# GSE_Analog_Remote_TOP_Schematic_v1_EasyE.net
KiCad netlist of a schematic drawn in EasyEDA
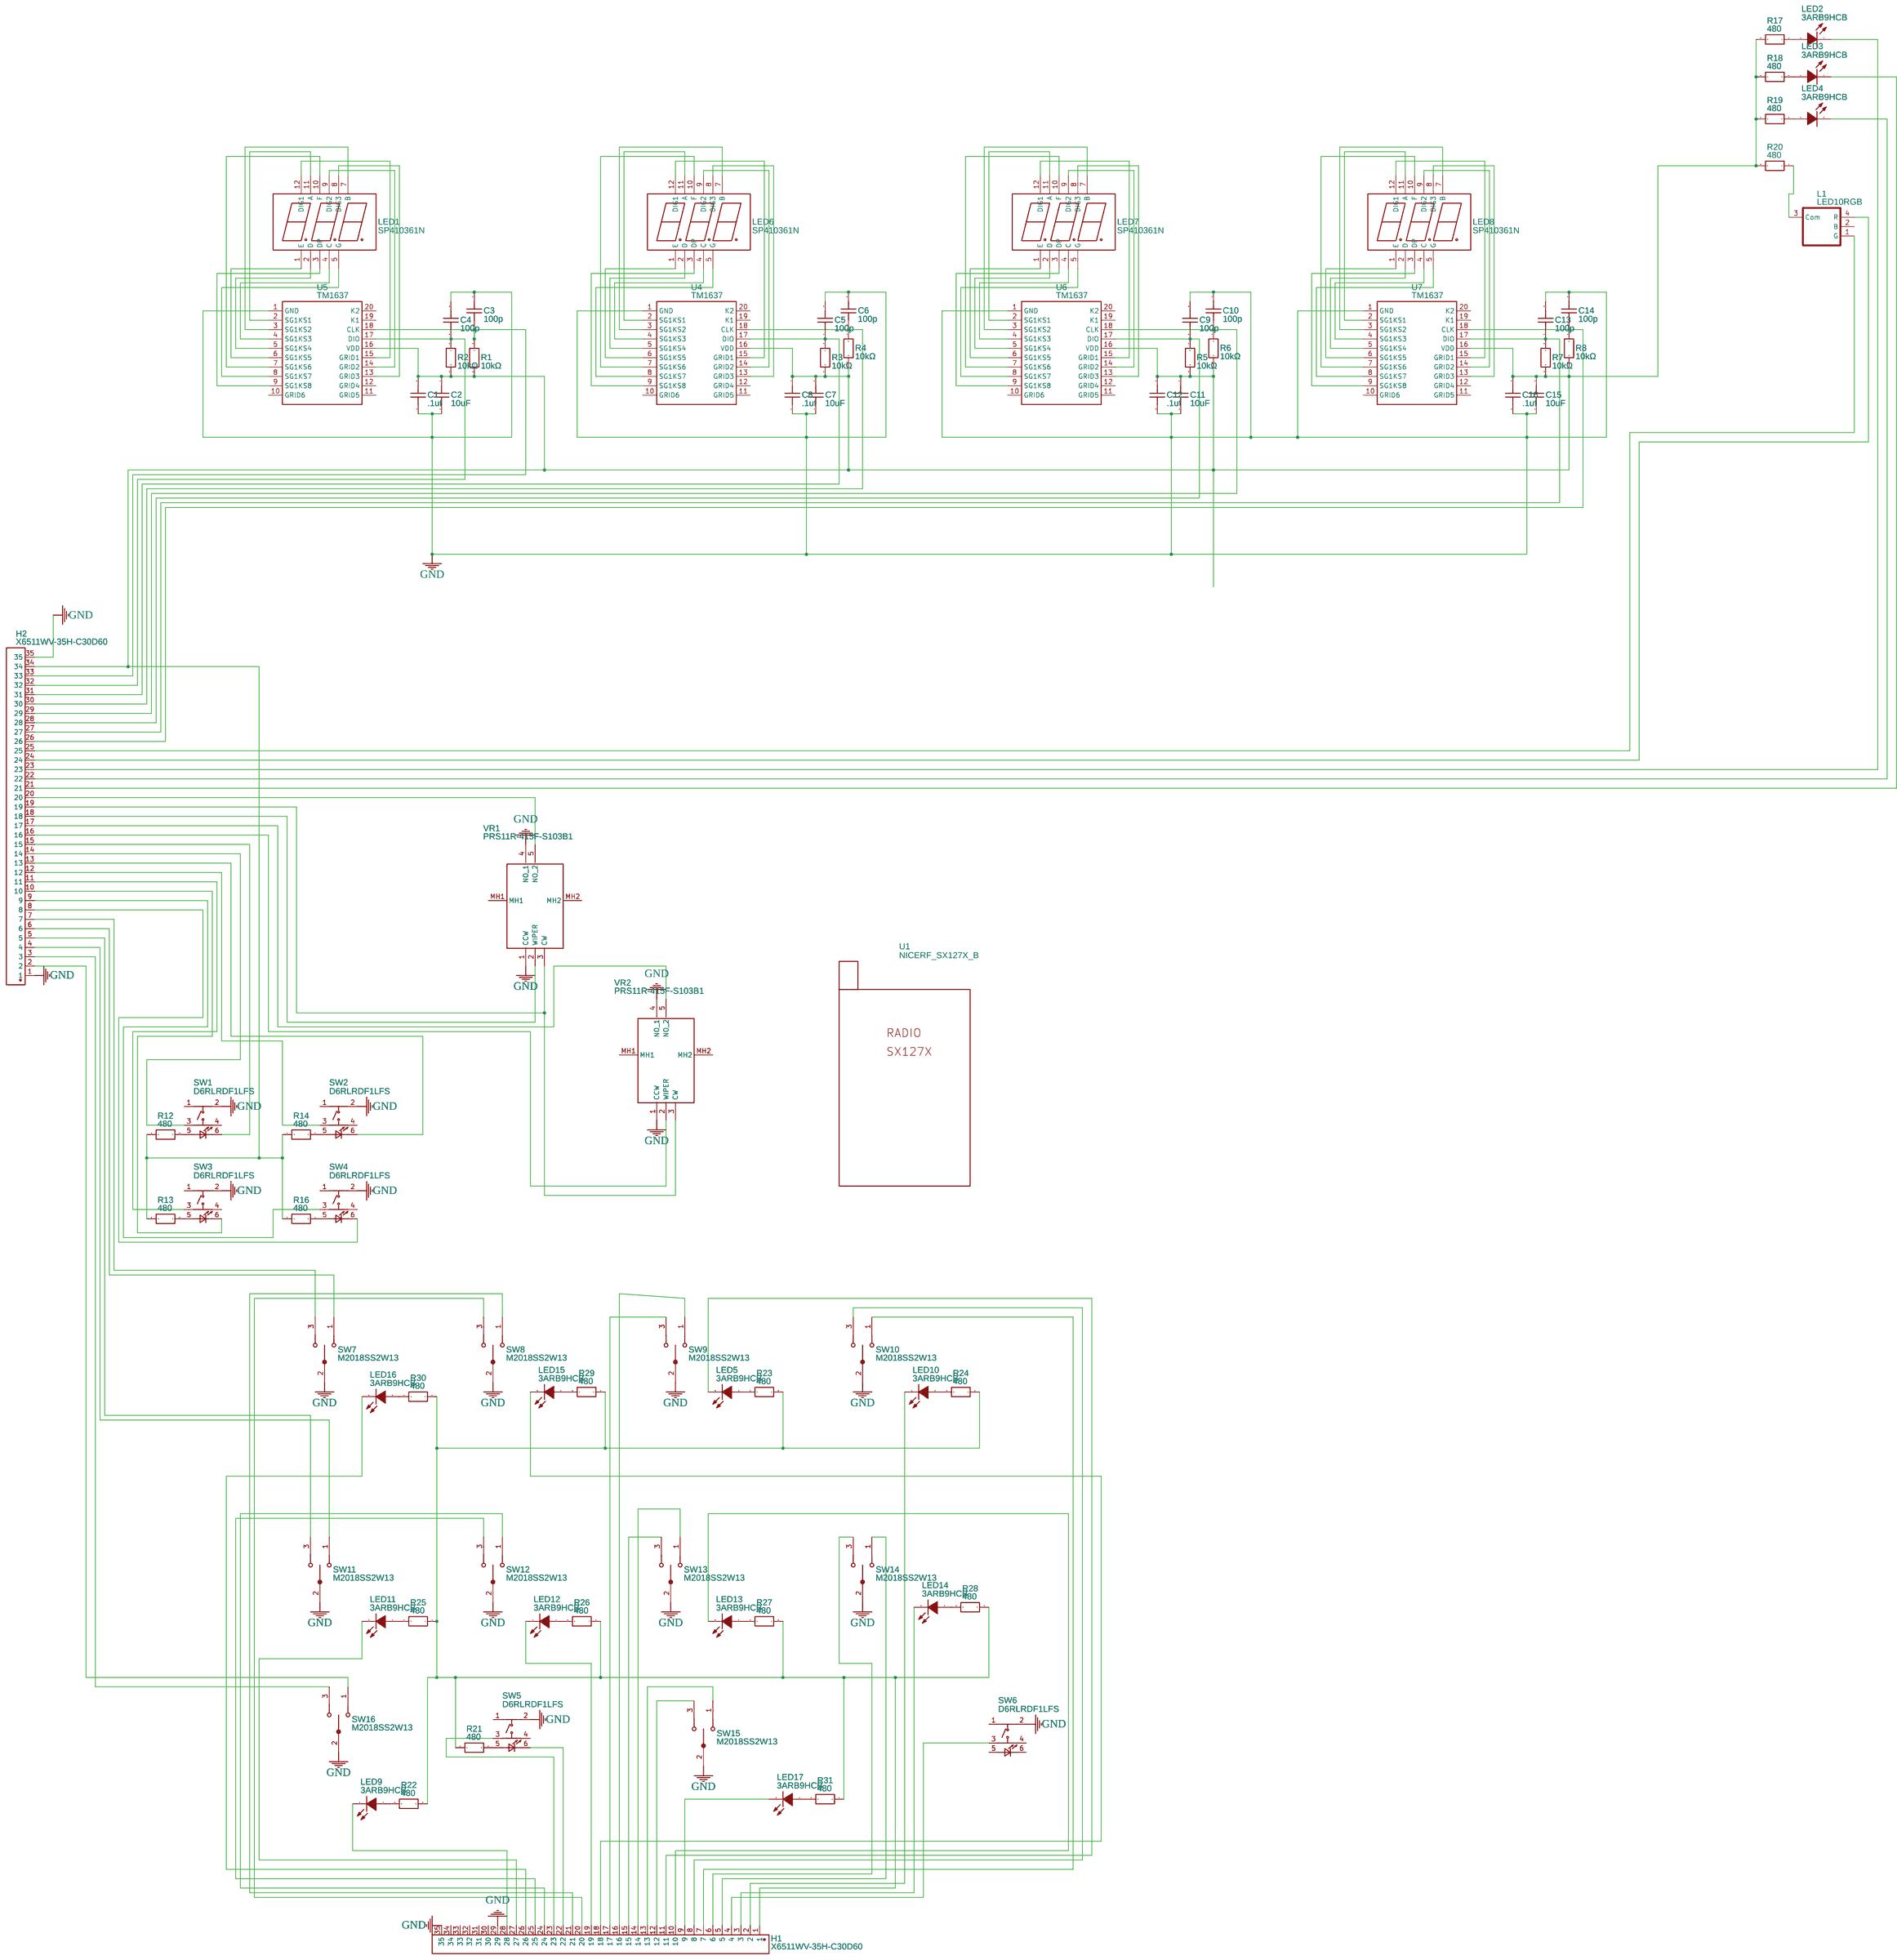
[diagram p0: schematic sheet]

(export (version "E")
  (design (tool "Eeschema 10.0.6"))
  (components
    (comp (ref "C1")
      (value ".1uf")
      (fields (field (name "Manufacturer") "SAMSUNG(三星)"))
      (libsource (lib "") (part "10UF"))
    )
    (comp (ref "C2")
      (value "10uF")
      (fields (field (name "Manufacturer") "SAMSUNG(三星)"))
      (libsource (lib "") (part "10UF"))
    )
    (comp (ref "C3")
      (value "100p")
      (fields (field (name "Manufacturer") "SAMSUNG(三星)"))
      (libsource (lib "") (part "10UF"))
    )
    (comp (ref "C4")
      (value "100p")
      (fields (field (name "Manufacturer") "SAMSUNG(三星)"))
      (libsource (lib "") (part "10UF"))
    )
    (comp (ref "C5")
      (value "100p")
      (fields (field (name "Manufacturer") "SAMSUNG(三星)"))
      (libsource (lib "") (part "10UF"))
    )
    (comp (ref "C6")
      (value "100p")
      (fields (field (name "Manufacturer") "SAMSUNG(三星)"))
      (libsource (lib "") (part "10UF"))
    )
    (comp (ref "C7")
      (value "10uF")
      (fields (field (name "Manufacturer") "SAMSUNG(三星)"))
      (libsource (lib "") (part "10UF"))
    )
    (comp (ref "C8")
      (value ".1uf")
      (fields (field (name "Manufacturer") "SAMSUNG(三星)"))
      (libsource (lib "") (part "10UF"))
    )
    (comp (ref "C9")
      (value "100p")
      (fields (field (name "Manufacturer") "SAMSUNG(三星)"))
      (libsource (lib "") (part "10UF"))
    )
    (comp (ref "C10")
      (value "100p")
      (fields (field (name "Manufacturer") "SAMSUNG(三星)"))
      (libsource (lib "") (part "10UF"))
    )
    (comp (ref "C11")
      (value "10uF")
      (fields (field (name "Manufacturer") "SAMSUNG(三星)"))
      (libsource (lib "") (part "10UF"))
    )
    (comp (ref "C12")
      (value ".1uf")
      (fields (field (name "Manufacturer") "SAMSUNG(三星)"))
      (libsource (lib "") (part "10UF"))
    )
    (comp (ref "C13")
      (value "100p")
      (fields (field (name "Manufacturer") "SAMSUNG(三星)"))
      (libsource (lib "") (part "10UF"))
    )
    (comp (ref "C14")
      (value "100p")
      (fields (field (name "Manufacturer") "SAMSUNG(三星)"))
      (libsource (lib "") (part "10UF"))
    )
    (comp (ref "C15")
      (value "10uF")
      (fields (field (name "Manufacturer") "SAMSUNG(三星)"))
      (libsource (lib "") (part "10UF"))
    )
    (comp (ref "C16")
      (value ".1uf")
      (fields (field (name "Manufacturer") "SAMSUNG(三星)"))
      (libsource (lib "") (part "10UF"))
    )
    (comp (ref "H1")
      (value "X6511WV-35H-C30D60")
      (fields (field (name "Manufacturer") "XKB Connectivity(中国星坤)"))
      (libsource (lib "") (part "X6511WV-35H-C30D60"))
    )
    (comp (ref "H2")
      (value "X6511WV-35H-C30D60")
      (fields (field (name "Manufacturer") "XKB Connectivity(中国星坤)"))
      (libsource (lib "") (part "X6511WV-35H-C30D60_1"))
    )
    (comp (ref "L1") (value "LED10RGB") (libsource (lib "") (part "LED10RGB")))
    (comp (ref "LED1")
      (value "SP410361N")
      (fields (field (name "Manufacturer") "ARKLED(方舟)"))
      (libsource (lib "") (part "SP410361N"))
    )
    (comp (ref "LED2")
      (value "3ARB9HCB")
      (fields (field (name "Manufacturer") "KENTO"))
      (libsource (lib "") (part "3ARB9HCB_1"))
    )
    (comp (ref "LED3")
      (value "3ARB9HCB")
      (fields (field (name "Manufacturer") "KENTO"))
      (libsource (lib "") (part "3ARB9HCB_1"))
    )
    (comp (ref "LED4")
      (value "3ARB9HCB")
      (fields (field (name "Manufacturer") "KENTO"))
      (libsource (lib "") (part "3ARB9HCB_1"))
    )
    (comp (ref "LED5")
      (value "3ARB9HCB")
      (fields (field (name "Manufacturer") "KENTO"))
      (libsource (lib "") (part "3ARB9HCB"))
    )
    (comp (ref "LED6")
      (value "SP410361N")
      (fields (field (name "Manufacturer") "ARKLED(方舟)"))
      (libsource (lib "") (part "SP410361N"))
    )
    (comp (ref "LED7")
      (value "SP410361N")
      (fields (field (name "Manufacturer") "ARKLED(方舟)"))
      (libsource (lib "") (part "SP410361N"))
    )
    (comp (ref "LED8")
      (value "SP410361N")
      (fields (field (name "Manufacturer") "ARKLED(方舟)"))
      (libsource (lib "") (part "SP410361N"))
    )
    (comp (ref "LED9")
      (value "3ARB9HCB")
      (fields (field (name "Manufacturer") "KENTO"))
      (libsource (lib "") (part "3ARB9HCB"))
    )
    (comp (ref "LED10")
      (value "3ARB9HCB")
      (fields (field (name "Manufacturer") "KENTO"))
      (libsource (lib "") (part "3ARB9HCB"))
    )
    (comp (ref "LED11")
      (value "3ARB9HCB")
      (fields (field (name "Manufacturer") "KENTO"))
      (libsource (lib "") (part "3ARB9HCB"))
    )
    (comp (ref "LED12")
      (value "3ARB9HCB")
      (fields (field (name "Manufacturer") "KENTO"))
      (libsource (lib "") (part "3ARB9HCB"))
    )
    (comp (ref "LED13")
      (value "3ARB9HCB")
      (fields (field (name "Manufacturer") "KENTO"))
      (libsource (lib "") (part "3ARB9HCB"))
    )
    (comp (ref "LED14")
      (value "3ARB9HCB")
      (fields (field (name "Manufacturer") "KENTO"))
      (libsource (lib "") (part "3ARB9HCB"))
    )
    (comp (ref "LED15")
      (value "3ARB9HCB")
      (fields (field (name "Manufacturer") "KENTO"))
      (libsource (lib "") (part "3ARB9HCB"))
    )
    (comp (ref "LED16")
      (value "3ARB9HCB")
      (fields (field (name "Manufacturer") "KENTO"))
      (libsource (lib "") (part "3ARB9HCB"))
    )
    (comp (ref "LED17")
      (value "3ARB9HCB")
      (fields (field (name "Manufacturer") "KENTO"))
      (libsource (lib "") (part "3ARB9HCB"))
    )
    (comp (ref "R1")
      (value "10kΩ")
      (fields (field (name "Manufacturer") "YAGEO(国巨)"))
      (libsource (lib "") (part "RE0603FRE0710KL"))
    )
    (comp (ref "R2")
      (value "10kΩ")
      (fields (field (name "Manufacturer") "YAGEO(国巨)"))
      (libsource (lib "") (part "RE0603FRE0710KL"))
    )
    (comp (ref "R3")
      (value "10kΩ")
      (fields (field (name "Manufacturer") "YAGEO(国巨)"))
      (libsource (lib "") (part "RE0603FRE0710KL"))
    )
    (comp (ref "R4")
      (value "10kΩ")
      (fields (field (name "Manufacturer") "YAGEO(国巨)"))
      (libsource (lib "") (part "RE0603FRE0710KL"))
    )
    (comp (ref "R5")
      (value "10kΩ")
      (fields (field (name "Manufacturer") "YAGEO(国巨)"))
      (libsource (lib "") (part "RE0603FRE0710KL"))
    )
    (comp (ref "R6")
      (value "10kΩ")
      (fields (field (name "Manufacturer") "YAGEO(国巨)"))
      (libsource (lib "") (part "RE0603FRE0710KL"))
    )
    (comp (ref "R7")
      (value "10kΩ")
      (fields (field (name "Manufacturer") "YAGEO(国巨)"))
      (libsource (lib "") (part "RE0603FRE0710KL"))
    )
    (comp (ref "R8")
      (value "10kΩ")
      (fields (field (name "Manufacturer") "YAGEO(国巨)"))
      (libsource (lib "") (part "RE0603FRE0710KL"))
    )
    (comp (ref "R12")
      (value "480")
      (fields (field (name "Manufacturer Part") "ERA6AEB202V") (field (name "Manufacturer") "PANASONIC"))
      (libsource (lib "") (part "ERA6AEB202V"))
    )
    (comp (ref "R13")
      (value "480")
      (fields (field (name "Manufacturer Part") "ERA6AEB202V") (field (name "Manufacturer") "PANASONIC"))
      (libsource (lib "") (part "ERA6AEB202V"))
    )
    (comp (ref "R14")
      (value "480")
      (fields (field (name "Manufacturer Part") "ERA6AEB202V") (field (name "Manufacturer") "PANASONIC"))
      (libsource (lib "") (part "ERA6AEB202V"))
    )
    (comp (ref "R16")
      (value "480")
      (fields (field (name "Manufacturer Part") "ERA6AEB202V") (field (name "Manufacturer") "PANASONIC"))
      (libsource (lib "") (part "ERA6AEB202V"))
    )
    (comp (ref "R17")
      (value "480")
      (fields (field (name "Manufacturer Part") "ERA6AEB202V") (field (name "Manufacturer") "PANASONIC"))
      (libsource (lib "") (part "ERA6AEB202V"))
    )
    (comp (ref "R18")
      (value "480")
      (fields (field (name "Manufacturer Part") "ERA6AEB202V") (field (name "Manufacturer") "PANASONIC"))
      (libsource (lib "") (part "ERA6AEB202V"))
    )
    (comp (ref "R19")
      (value "480")
      (fields (field (name "Manufacturer Part") "ERA6AEB202V") (field (name "Manufacturer") "PANASONIC"))
      (libsource (lib "") (part "ERA6AEB202V"))
    )
    (comp (ref "R20")
      (value "480")
      (fields (field (name "Manufacturer Part") "ERA6AEB202V") (field (name "Manufacturer") "PANASONIC"))
      (libsource (lib "") (part "ERA6AEB202V"))
    )
    (comp (ref "R21")
      (value "480")
      (fields (field (name "Manufacturer Part") "ERA6AEB202V") (field (name "Manufacturer") "PANASONIC"))
      (libsource (lib "") (part "ERA6AEB202V"))
    )
    (comp (ref "R22")
      (value "480")
      (fields (field (name "Manufacturer Part") "ERA6AEB202V") (field (name "Manufacturer") "PANASONIC"))
      (libsource (lib "") (part "ERA6AEB202V"))
    )
    (comp (ref "R23")
      (value "480")
      (fields (field (name "Manufacturer Part") "ERA6AEB202V") (field (name "Manufacturer") "PANASONIC"))
      (libsource (lib "") (part "ERA6AEB202V"))
    )
    (comp (ref "R24")
      (value "480")
      (fields (field (name "Manufacturer Part") "ERA6AEB202V") (field (name "Manufacturer") "PANASONIC"))
      (libsource (lib "") (part "ERA6AEB202V"))
    )
    (comp (ref "R25")
      (value "480")
      (fields (field (name "Manufacturer Part") "ERA6AEB202V") (field (name "Manufacturer") "PANASONIC"))
      (libsource (lib "") (part "ERA6AEB202V"))
    )
    (comp (ref "R26")
      (value "480")
      (fields (field (name "Manufacturer Part") "ERA6AEB202V") (field (name "Manufacturer") "PANASONIC"))
      (libsource (lib "") (part "ERA6AEB202V"))
    )
    (comp (ref "R27")
      (value "480")
      (fields (field (name "Manufacturer Part") "ERA6AEB202V") (field (name "Manufacturer") "PANASONIC"))
      (libsource (lib "") (part "ERA6AEB202V"))
    )
    (comp (ref "R28")
      (value "480")
      (fields (field (name "Manufacturer Part") "ERA6AEB202V") (field (name "Manufacturer") "PANASONIC"))
      (libsource (lib "") (part "ERA6AEB202V"))
    )
    (comp (ref "R29")
      (value "480")
      (fields (field (name "Manufacturer Part") "ERA6AEB202V") (field (name "Manufacturer") "PANASONIC"))
      (libsource (lib "") (part "ERA6AEB202V"))
    )
    (comp (ref "R30")
      (value "480")
      (fields (field (name "Manufacturer Part") "ERA6AEB202V") (field (name "Manufacturer") "PANASONIC"))
      (libsource (lib "") (part "ERA6AEB202V"))
    )
    (comp (ref "R31")
      (value "480")
      (fields (field (name "Manufacturer Part") "ERA6AEB202V") (field (name "Manufacturer") "PANASONIC"))
      (libsource (lib "") (part "ERA6AEB202V"))
    )
    (comp (ref "SW1")
      (value "D6RLRDF1LFS")
      (fields (field (name "Manufacturer") "C&K"))
      (libsource (lib "") (part "D6RLRDF1LFS"))
    )
    (comp (ref "SW2")
      (value "D6RLRDF1LFS")
      (fields (field (name "Manufacturer") "C&K"))
      (libsource (lib "") (part "D6RLRDF1LFS"))
    )
    (comp (ref "SW3")
      (value "D6RLRDF1LFS")
      (fields (field (name "Manufacturer") "C&K"))
      (libsource (lib "") (part "D6RLRDF1LFS"))
    )
    (comp (ref "SW4")
      (value "D6RLRDF1LFS")
      (fields (field (name "Manufacturer") "C&K"))
      (libsource (lib "") (part "D6RLRDF1LFS"))
    )
    (comp (ref "SW5")
      (value "D6RLRDF1LFS")
      (fields (field (name "Manufacturer") "C&K"))
      (libsource (lib "") (part "D6RLRDF1LFS"))
    )
    (comp (ref "SW6")
      (value "D6RLRDF1LFS")
      (fields (field (name "Manufacturer") "C&K"))
      (libsource (lib "") (part "D6RLRDF1LFS"))
    )
    (comp (ref "SW7") (value "M2018SS2W13") (libsource (lib "") (part "M2018SS2W13")))
    (comp (ref "SW8") (value "M2018SS2W13") (libsource (lib "") (part "M2018SS2W13")))
    (comp (ref "SW9") (value "M2018SS2W13") (libsource (lib "") (part "M2018SS2W13")))
    (comp (ref "SW10") (value "M2018SS2W13") (libsource (lib "") (part "M2018SS2W13")))
    (comp (ref "SW11") (value "M2018SS2W13") (libsource (lib "") (part "M2018SS2W13")))
    (comp (ref "SW12") (value "M2018SS2W13") (libsource (lib "") (part "M2018SS2W13")))
    (comp (ref "SW13") (value "M2018SS2W13") (libsource (lib "") (part "M2018SS2W13")))
    (comp (ref "SW14") (value "M2018SS2W13") (libsource (lib "") (part "M2018SS2W13")))
    (comp (ref "SW15") (value "M2018SS2W13") (libsource (lib "") (part "M2018SS2W13")))
    (comp (ref "SW16") (value "M2018SS2W13") (libsource (lib "") (part "M2018SS2W13")))
    (comp (ref "U1") (value "NICERF_SX127X_B") (libsource (lib "") (part "NICERF_SX127X_B")))
    (comp (ref "U4")
      (value "TM1637")
      (fields (field (name "Manufacturer") "TM(天微)"))
      (libsource (lib "") (part "TM1637"))
    )
    (comp (ref "U5")
      (value "TM1637")
      (fields (field (name "Manufacturer") "TM(天微)"))
      (libsource (lib "") (part "TM1637"))
    )
    (comp (ref "U6")
      (value "TM1637")
      (fields (field (name "Manufacturer") "TM(天微)"))
      (libsource (lib "") (part "TM1637"))
    )
    (comp (ref "U7")
      (value "TM1637")
      (fields (field (name "Manufacturer") "TM(天微)"))
      (libsource (lib "") (part "TM1637"))
    )
    (comp (ref "VR1")
      (value "PRS11R-415F-S103B1")
      (fields (field (name "Manufacturer") "BOURNS"))
      (libsource (lib "") (part "PRS11R-415F-S103B1"))
    )
    (comp (ref "VR2")
      (value "PRS11R-415F-S103B1")
      (fields (field (name "Manufacturer") "BOURNS"))
      (libsource (lib "") (part "PRS11R-415F-S103B1"))
    )
  )
  (nets
    (net (code "1") (name "GND") (class "Default")
      (node (ref "C1") (pin "1") (pinfunction "1_1") (pintype "unspecified"))
      (node (ref "C10") (pin "2") (pinfunction "2_2") (pintype "unspecified"))
      (node (ref "C11") (pin "1") (pinfunction "1_1") (pintype "unspecified"))
      (node (ref "C12") (pin "1") (pinfunction "1_1") (pintype "unspecified"))
      (node (ref "C13") (pin "2") (pinfunction "2_2") (pintype "unspecified"))
      (node (ref "C14") (pin "2") (pinfunction "2_2") (pintype "unspecified"))
      (node (ref "C15") (pin "1") (pinfunction "1_1") (pintype "unspecified"))
      (node (ref "C16") (pin "1") (pinfunction "1_1") (pintype "unspecified"))
      (node (ref "C2") (pin "1") (pinfunction "1_1") (pintype "unspecified"))
      (node (ref "C3") (pin "2") (pinfunction "2_2") (pintype "unspecified"))
      (node (ref "C4") (pin "2") (pinfunction "2_2") (pintype "unspecified"))
      (node (ref "C5") (pin "2") (pinfunction "2_2") (pintype "unspecified"))
      (node (ref "C6") (pin "2") (pinfunction "2_2") (pintype "unspecified"))
      (node (ref "C7") (pin "1") (pinfunction "1_1") (pintype "unspecified"))
      (node (ref "C8") (pin "1") (pinfunction "1_1") (pintype "unspecified"))
      (node (ref "C9") (pin "2") (pinfunction "2_2") (pintype "unspecified"))
      (node (ref "H1") (pin "29") (pinfunction "29_29") (pintype "unspecified"))
      (node (ref "H1") (pin "35") (pinfunction "35_35") (pintype "unspecified"))
      (node (ref "H2") (pin "1") (pinfunction "1_1") (pintype "unspecified"))
      (node (ref "H2") (pin "35") (pinfunction "35_35") (pintype "unspecified"))
      (node (ref "SW1") (pin "2") (pinfunction "2_2") (pintype "unspecified"))
      (node (ref "SW10") (pin "2") (pinfunction "2_2") (pintype "unspecified"))
      (node (ref "SW11") (pin "2") (pinfunction "2_2") (pintype "unspecified"))
      (node (ref "SW12") (pin "2") (pinfunction "2_2") (pintype "unspecified"))
      (node (ref "SW13") (pin "2") (pinfunction "2_2") (pintype "unspecified"))
      (node (ref "SW14") (pin "2") (pinfunction "2_2") (pintype "unspecified"))
      (node (ref "SW15") (pin "2") (pinfunction "2_2") (pintype "unspecified"))
      (node (ref "SW16") (pin "2") (pinfunction "2_2") (pintype "unspecified"))
      (node (ref "SW2") (pin "2") (pinfunction "2_2") (pintype "unspecified"))
      (node (ref "SW3") (pin "2") (pinfunction "2_2") (pintype "unspecified"))
      (node (ref "SW4") (pin "2") (pinfunction "2_2") (pintype "unspecified"))
      (node (ref "SW5") (pin "2") (pinfunction "2_2") (pintype "unspecified"))
      (node (ref "SW6") (pin "2") (pinfunction "2_2") (pintype "unspecified"))
      (node (ref "SW7") (pin "2") (pinfunction "2_2") (pintype "unspecified"))
      (node (ref "SW8") (pin "2") (pinfunction "2_2") (pintype "unspecified"))
      (node (ref "SW9") (pin "2") (pinfunction "2_2") (pintype "unspecified"))
      (node (ref "U4") (pin "1") (pinfunction "GND_1") (pintype "unspecified"))
      (node (ref "U5") (pin "1") (pinfunction "GND_1") (pintype "unspecified"))
      (node (ref "U6") (pin "1") (pinfunction "GND_1") (pintype "unspecified"))
      (node (ref "U7") (pin "1") (pinfunction "GND_1") (pintype "unspecified"))
      (node (ref "VR1") (pin "1") (pinfunction "CCW_1") (pintype "bidirectional"))
      (node (ref "VR1") (pin "4") (pinfunction "NO_1_4") (pintype "bidirectional"))
      (node (ref "VR2") (pin "1") (pinfunction "CCW_1") (pintype "bidirectional"))
      (node (ref "VR2") (pin "4") (pinfunction "NO_1_4") (pintype "bidirectional"))
    )
    (net (code "2") (name "Net-(H1-Pad1)") (class "Default")
      (node (ref "H1") (pin "1") (pinfunction "1_1") (pintype "unspecified"))
      (node (ref "R21") (pin "2") (pinfunction "2_2") (pintype "unspecified"))
      (node (ref "R22") (pin "1") (pinfunction "1_1") (pintype "unspecified"))
      (node (ref "R23") (pin "1") (pinfunction "1_1") (pintype "unspecified"))
      (node (ref "R24") (pin "1") (pinfunction "1_1") (pintype "unspecified"))
      (node (ref "R25") (pin "1") (pinfunction "1_1") (pintype "unspecified"))
      (node (ref "R26") (pin "1") (pinfunction "1_1") (pintype "unspecified"))
      (node (ref "R27") (pin "1") (pinfunction "1_1") (pintype "unspecified"))
      (node (ref "R28") (pin "1") (pinfunction "1_1") (pintype "unspecified"))
      (node (ref "R29") (pin "1") (pinfunction "1_1") (pintype "unspecified"))
      (node (ref "R30") (pin "1") (pinfunction "1_1") (pintype "unspecified"))
      (node (ref "R31") (pin "1") (pinfunction "1_1") (pintype "unspecified"))
    )
    (net (code "3") (name "Net-(H1-Pad4)") (class "Default")
      (node (ref "H1") (pin "4") (pinfunction "4_4") (pintype "unspecified"))
      (node (ref "SW6") (pin "3") (pinfunction "3_3") (pintype "unspecified"))
    )
    (net (code "4") (name "Net-(H1-Pad5)") (class "Default")
      (node (ref "H1") (pin "5") (pinfunction "5_5") (pintype "unspecified"))
      (node (ref "SW14") (pin "1") (pinfunction "1_1") (pintype "unspecified"))
    )
    (net (code "5") (name "Net-(H1-Pad6)") (class "Default")
      (node (ref "H1") (pin "6") (pinfunction "6_6") (pintype "unspecified"))
      (node (ref "SW14") (pin "3") (pinfunction "3_3") (pintype "unspecified"))
    )
    (net (code "6") (name "Net-(H1-Pad7)") (class "Default")
      (node (ref "H1") (pin "7") (pinfunction "7_7") (pintype "unspecified"))
      (node (ref "SW10") (pin "1") (pinfunction "1_1") (pintype "unspecified"))
    )
    (net (code "7") (name "Net-(H1-Pad8)") (class "Default")
      (node (ref "H1") (pin "8") (pinfunction "8_8") (pintype "unspecified"))
      (node (ref "SW10") (pin "3") (pinfunction "3_3") (pintype "unspecified"))
    )
    (net (code "8") (name "Net-(H1-Pad12)") (class "Default")
      (node (ref "H1") (pin "12") (pinfunction "12_12") (pintype "unspecified"))
      (node (ref "SW15") (pin "3") (pinfunction "3_3") (pintype "unspecified"))
    )
    (net (code "9") (name "Net-(H1-Pad13)") (class "Default")
      (node (ref "H1") (pin "13") (pinfunction "13_13") (pintype "unspecified"))
      (node (ref "SW15") (pin "1") (pinfunction "1_1") (pintype "unspecified"))
    )
    (net (code "10") (name "Net-(H1-Pad14)") (class "Default")
      (node (ref "H1") (pin "14") (pinfunction "14_14") (pintype "unspecified"))
      (node (ref "SW13") (pin "1") (pinfunction "1_1") (pintype "unspecified"))
    )
    (net (code "11") (name "Net-(H1-Pad15)") (class "Default")
      (node (ref "H1") (pin "15") (pinfunction "15_15") (pintype "unspecified"))
      (node (ref "SW13") (pin "3") (pinfunction "3_3") (pintype "unspecified"))
    )
    (net (code "12") (name "Net-(H1-Pad16)") (class "Default")
      (node (ref "H1") (pin "16") (pinfunction "16_16") (pintype "unspecified"))
      (node (ref "SW9") (pin "1") (pinfunction "1_1") (pintype "unspecified"))
    )
    (net (code "13") (name "Net-(H1-Pad17)") (class "Default")
      (node (ref "H1") (pin "17") (pinfunction "17_17") (pintype "unspecified"))
      (node (ref "SW9") (pin "3") (pinfunction "3_3") (pintype "unspecified"))
    )
    (net (code "14") (name "Net-(H1-Pad20)") (class "Default")
      (node (ref "H1") (pin "20") (pinfunction "20_20") (pintype "unspecified"))
      (node (ref "SW8") (pin "3") (pinfunction "3_3") (pintype "unspecified"))
    )
    (net (code "15") (name "Net-(H1-Pad21)") (class "Default")
      (node (ref "H1") (pin "21") (pinfunction "21_21") (pintype "unspecified"))
      (node (ref "SW8") (pin "1") (pinfunction "1_1") (pintype "unspecified"))
    )
    (net (code "16") (name "Net-(H1-Pad22)") (class "Default")
      (node (ref "H1") (pin "22") (pinfunction "22_22") (pintype "unspecified"))
      (node (ref "SW5") (pin "6") (pinfunction "6_6") (pintype "unspecified"))
    )
    (net (code "17") (name "Net-(H1-Pad23)") (class "Default")
      (node (ref "H1") (pin "23") (pinfunction "23_23") (pintype "unspecified"))
      (node (ref "SW5") (pin "3") (pinfunction "3_3") (pintype "unspecified"))
    )
    (net (code "18") (name "Net-(H1-Pad24)") (class "Default")
      (node (ref "H1") (pin "24") (pinfunction "24_24") (pintype "unspecified"))
      (node (ref "SW12") (pin "1") (pinfunction "1_1") (pintype "unspecified"))
    )
    (net (code "19") (name "Net-(H1-Pad25)") (class "Default")
      (node (ref "H1") (pin "25") (pinfunction "25_25") (pintype "unspecified"))
      (node (ref "SW12") (pin "3") (pinfunction "3_3") (pintype "unspecified"))
    )
    (net (code "20") (name "Net-(H2-Pad2)") (class "Default")
      (node (ref "H2") (pin "2") (pinfunction "2_2") (pintype "unspecified"))
      (node (ref "SW16") (pin "1") (pinfunction "1_1") (pintype "unspecified"))
    )
    (net (code "21") (name "Net-(H2-Pad3)") (class "Default")
      (node (ref "H2") (pin "3") (pinfunction "3_3") (pintype "unspecified"))
      (node (ref "SW16") (pin "3") (pinfunction "3_3") (pintype "unspecified"))
    )
    (net (code "22") (name "Net-(H2-Pad4)") (class "Default")
      (node (ref "H2") (pin "4") (pinfunction "4_4") (pintype "unspecified"))
      (node (ref "SW11") (pin "1") (pinfunction "1_1") (pintype "unspecified"))
    )
    (net (code "23") (name "Net-(H2-Pad5)") (class "Default")
      (node (ref "H2") (pin "5") (pinfunction "5_5") (pintype "unspecified"))
      (node (ref "SW11") (pin "3") (pinfunction "3_3") (pintype "unspecified"))
    )
    (net (code "24") (name "Net-(H2-Pad6)") (class "Default")
      (node (ref "H2") (pin "6") (pinfunction "6_6") (pintype "unspecified"))
      (node (ref "SW7") (pin "1") (pinfunction "1_1") (pintype "unspecified"))
    )
    (net (code "25") (name "Net-(H2-Pad7)") (class "Default")
      (node (ref "H2") (pin "7") (pinfunction "7_7") (pintype "unspecified"))
      (node (ref "SW7") (pin "3") (pinfunction "3_3") (pintype "unspecified"))
    )
    (net (code "26") (name "Net-(H2-Pad8)") (class "Default")
      (node (ref "H2") (pin "8") (pinfunction "8_8") (pintype "unspecified"))
      (node (ref "SW4") (pin "6") (pinfunction "6_6") (pintype "unspecified"))
    )
    (net (code "27") (name "Net-(H2-Pad9)") (class "Default")
      (node (ref "H2") (pin "9") (pinfunction "9_9") (pintype "unspecified"))
      (node (ref "SW4") (pin "3") (pinfunction "3_3") (pintype "unspecified"))
    )
    (net (code "28") (name "Net-(H2-Pad10)") (class "Default")
      (node (ref "H2") (pin "10") (pinfunction "10_10") (pintype "unspecified"))
      (node (ref "SW3") (pin "6") (pinfunction "6_6") (pintype "unspecified"))
    )
    (net (code "29") (name "Net-(H2-Pad11)") (class "Default")
      (node (ref "H2") (pin "11") (pinfunction "11_11") (pintype "unspecified"))
      (node (ref "SW3") (pin "3") (pinfunction "3_3") (pintype "unspecified"))
    )
    (net (code "30") (name "Net-(H2-Pad12)") (class "Default")
      (node (ref "H2") (pin "12") (pinfunction "12_12") (pintype "unspecified"))
      (node (ref "SW2") (pin "3") (pinfunction "3_3") (pintype "unspecified"))
    )
    (net (code "31") (name "Net-(H2-Pad13)") (class "Default")
      (node (ref "H2") (pin "13") (pinfunction "13_13") (pintype "unspecified"))
      (node (ref "SW2") (pin "6") (pinfunction "6_6") (pintype "unspecified"))
    )
    (net (code "32") (name "Net-(H2-Pad14)") (class "Default")
      (node (ref "H2") (pin "14") (pinfunction "14_14") (pintype "unspecified"))
      (node (ref "SW1") (pin "3") (pinfunction "3_3") (pintype "unspecified"))
    )
    (net (code "33") (name "Net-(H2-Pad15)") (class "Default")
      (node (ref "H2") (pin "15") (pinfunction "15_15") (pintype "unspecified"))
      (node (ref "SW1") (pin "6") (pinfunction "6_6") (pintype "unspecified"))
    )
    (net (code "34") (name "Net-(L1-Com)") (class "Default")
      (node (ref "L1") (pin "3") (pinfunction "Com_3") (pintype "unspecified"))
      (node (ref "R20") (pin "1") (pinfunction "1_1") (pintype "unspecified"))
    )
    (net (code "35") (name "Net-(L1-G)") (class "Default")
      (node (ref "H2") (pin "25") (pinfunction "25_25") (pintype "unspecified"))
      (node (ref "L1") (pin "1") (pinfunction "G_1") (pintype "unspecified"))
    )
    (net (code "36") (name "Net-(L1-R)") (class "Default")
      (node (ref "H2") (pin "24") (pinfunction "24_24") (pintype "unspecified"))
      (node (ref "L1") (pin "4") (pinfunction "R_4") (pintype "unspecified"))
    )
    (net (code "37") (name "Net-(LED1-A)") (class "Default")
      (node (ref "LED1") (pin "11") (pinfunction "A_11") (pintype "unspecified"))
      (node (ref "U5") (pin "2") (pinfunction "SG1KS1_2") (pintype "unspecified"))
    )
    (net (code "38") (name "Net-(LED1-B)") (class "Default")
      (node (ref "LED1") (pin "7") (pinfunction "B_7") (pintype "unspecified"))
      (node (ref "U5") (pin "3") (pinfunction "SG1KS2_3") (pintype "unspecified"))
    )
    (net (code "39") (name "Net-(LED1-C)") (class "Default")
      (node (ref "LED1") (pin "4") (pinfunction "C_4") (pintype "unspecified"))
      (node (ref "U5") (pin "4") (pinfunction "SG1KS3_4") (pintype "unspecified"))
    )
    (net (code "40") (name "Net-(LED1-D)") (class "Default")
      (node (ref "LED1") (pin "2") (pinfunction "D_2") (pintype "unspecified"))
      (node (ref "U5") (pin "5") (pinfunction "SG1KS4_5") (pintype "unspecified"))
    )
    (net (code "41") (name "Net-(LED1-DIG1)") (class "Default")
      (node (ref "LED1") (pin "12") (pinfunction "DIG1_12") (pintype "unspecified"))
      (node (ref "U5") (pin "15") (pinfunction "GRID1_15") (pintype "unspecified"))
    )
    (net (code "42") (name "Net-(LED1-DIG2)") (class "Default")
      (node (ref "LED1") (pin "9") (pinfunction "DIG2_9") (pintype "unspecified"))
      (node (ref "U5") (pin "14") (pinfunction "GRID2_14") (pintype "unspecified"))
    )
    (net (code "43") (name "Net-(LED1-DIG3)") (class "Default")
      (node (ref "LED1") (pin "8") (pinfunction "DIG3_8") (pintype "unspecified"))
      (node (ref "U5") (pin "13") (pinfunction "GRID3_13") (pintype "unspecified"))
    )
    (net (code "44") (name "Net-(LED1-DP)") (class "Default")
      (node (ref "LED1") (pin "3") (pinfunction "DP_3") (pintype "unspecified"))
      (node (ref "U5") (pin "9") (pinfunction "SG1KS8_9") (pintype "unspecified"))
    )
    (net (code "45") (name "Net-(LED1-E)") (class "Default")
      (node (ref "LED1") (pin "1") (pinfunction "E_1") (pintype "unspecified"))
      (node (ref "U5") (pin "6") (pinfunction "SG1KS5_6") (pintype "unspecified"))
    )
    (net (code "46") (name "Net-(LED1-F)") (class "Default")
      (node (ref "LED1") (pin "10") (pinfunction "F_10") (pintype "unspecified"))
      (node (ref "U5") (pin "7") (pinfunction "SG1KS6_7") (pintype "unspecified"))
    )
    (net (code "47") (name "Net-(LED1-G)") (class "Default")
      (node (ref "LED1") (pin "5") (pinfunction "G_5") (pintype "unspecified"))
      (node (ref "U5") (pin "8") (pinfunction "SG1KS7_8") (pintype "unspecified"))
    )
    (net (code "48") (name "Net-(LED2-A)") (class "Default")
      (node (ref "LED2") (pin "1") (pinfunction "A_1") (pintype "unspecified"))
      (node (ref "R17") (pin "1") (pinfunction "1_1") (pintype "unspecified"))
    )
    (net (code "49") (name "Net-(LED2-K)") (class "Default")
      (node (ref "H2") (pin "23") (pinfunction "23_23") (pintype "unspecified"))
      (node (ref "LED2") (pin "2") (pinfunction "K_2") (pintype "unspecified"))
    )
    (net (code "50") (name "Net-(LED3-A)") (class "Default")
      (node (ref "LED3") (pin "1") (pinfunction "A_1") (pintype "unspecified"))
      (node (ref "R18") (pin "1") (pinfunction "1_1") (pintype "unspecified"))
    )
    (net (code "51") (name "Net-(LED3-K)") (class "Default")
      (node (ref "H2") (pin "21") (pinfunction "21_21") (pintype "unspecified"))
      (node (ref "LED3") (pin "2") (pinfunction "K_2") (pintype "unspecified"))
    )
    (net (code "52") (name "Net-(LED4-A)") (class "Default")
      (node (ref "LED4") (pin "1") (pinfunction "A_1") (pintype "unspecified"))
      (node (ref "R19") (pin "1") (pinfunction "1_1") (pintype "unspecified"))
    )
    (net (code "53") (name "Net-(LED4-K)") (class "Default")
      (node (ref "H2") (pin "22") (pinfunction "22_22") (pintype "unspecified"))
      (node (ref "LED4") (pin "2") (pinfunction "K_2") (pintype "unspecified"))
    )
    (net (code "54") (name "Net-(LED5-A)") (class "Default")
      (node (ref "LED5") (pin "1") (pinfunction "A_1") (pintype "unspecified"))
      (node (ref "R23") (pin "2") (pinfunction "2_2") (pintype "unspecified"))
    )
    (net (code "55") (name "Net-(LED5-K)") (class "Default")
      (node (ref "H1") (pin "11") (pinfunction "11_11") (pintype "unspecified"))
      (node (ref "LED5") (pin "2") (pinfunction "K_2") (pintype "unspecified"))
    )
    (net (code "56") (name "Net-(LED6-A)") (class "Default")
      (node (ref "LED6") (pin "11") (pinfunction "A_11") (pintype "unspecified"))
      (node (ref "U4") (pin "2") (pinfunction "SG1KS1_2") (pintype "unspecified"))
    )
    (net (code "57") (name "Net-(LED6-B)") (class "Default")
      (node (ref "LED6") (pin "7") (pinfunction "B_7") (pintype "unspecified"))
      (node (ref "U4") (pin "3") (pinfunction "SG1KS2_3") (pintype "unspecified"))
    )
    (net (code "58") (name "Net-(LED6-C)") (class "Default")
      (node (ref "LED6") (pin "4") (pinfunction "C_4") (pintype "unspecified"))
      (node (ref "U4") (pin "4") (pinfunction "SG1KS3_4") (pintype "unspecified"))
    )
    (net (code "59") (name "Net-(LED6-D)") (class "Default")
      (node (ref "LED6") (pin "2") (pinfunction "D_2") (pintype "unspecified"))
      (node (ref "U4") (pin "5") (pinfunction "SG1KS4_5") (pintype "unspecified"))
    )
    (net (code "60") (name "Net-(LED6-DIG1)") (class "Default")
      (node (ref "LED6") (pin "12") (pinfunction "DIG1_12") (pintype "unspecified"))
      (node (ref "U4") (pin "15") (pinfunction "GRID1_15") (pintype "unspecified"))
    )
    (net (code "61") (name "Net-(LED6-DIG2)") (class "Default")
      (node (ref "LED6") (pin "9") (pinfunction "DIG2_9") (pintype "unspecified"))
      (node (ref "U4") (pin "14") (pinfunction "GRID2_14") (pintype "unspecified"))
    )
    (net (code "62") (name "Net-(LED6-DIG3)") (class "Default")
      (node (ref "LED6") (pin "8") (pinfunction "DIG3_8") (pintype "unspecified"))
      (node (ref "U4") (pin "13") (pinfunction "GRID3_13") (pintype "unspecified"))
    )
    (net (code "63") (name "Net-(LED6-DP)") (class "Default")
      (node (ref "LED6") (pin "3") (pinfunction "DP_3") (pintype "unspecified"))
      (node (ref "U4") (pin "9") (pinfunction "SG1KS8_9") (pintype "unspecified"))
    )
    (net (code "64") (name "Net-(LED6-E)") (class "Default")
      (node (ref "LED6") (pin "1") (pinfunction "E_1") (pintype "unspecified"))
      (node (ref "U4") (pin "6") (pinfunction "SG1KS5_6") (pintype "unspecified"))
    )
    (net (code "65") (name "Net-(LED6-F)") (class "Default")
      (node (ref "LED6") (pin "10") (pinfunction "F_10") (pintype "unspecified"))
      (node (ref "U4") (pin "7") (pinfunction "SG1KS6_7") (pintype "unspecified"))
    )
    (net (code "66") (name "Net-(LED6-G)") (class "Default")
      (node (ref "LED6") (pin "5") (pinfunction "G_5") (pintype "unspecified"))
      (node (ref "U4") (pin "8") (pinfunction "SG1KS7_8") (pintype "unspecified"))
    )
    (net (code "67") (name "Net-(LED7-A)") (class "Default")
      (node (ref "LED7") (pin "11") (pinfunction "A_11") (pintype "unspecified"))
      (node (ref "U6") (pin "2") (pinfunction "SG1KS1_2") (pintype "unspecified"))
    )
    (net (code "68") (name "Net-(LED7-B)") (class "Default")
      (node (ref "LED7") (pin "7") (pinfunction "B_7") (pintype "unspecified"))
      (node (ref "U6") (pin "3") (pinfunction "SG1KS2_3") (pintype "unspecified"))
    )
    (net (code "69") (name "Net-(LED7-C)") (class "Default")
      (node (ref "LED7") (pin "4") (pinfunction "C_4") (pintype "unspecified"))
      (node (ref "U6") (pin "4") (pinfunction "SG1KS3_4") (pintype "unspecified"))
    )
    (net (code "70") (name "Net-(LED7-D)") (class "Default")
      (node (ref "LED7") (pin "2") (pinfunction "D_2") (pintype "unspecified"))
      (node (ref "U6") (pin "5") (pinfunction "SG1KS4_5") (pintype "unspecified"))
    )
    (net (code "71") (name "Net-(LED7-DIG1)") (class "Default")
      (node (ref "LED7") (pin "12") (pinfunction "DIG1_12") (pintype "unspecified"))
      (node (ref "U6") (pin "15") (pinfunction "GRID1_15") (pintype "unspecified"))
    )
    (net (code "72") (name "Net-(LED7-DIG2)") (class "Default")
      (node (ref "LED7") (pin "9") (pinfunction "DIG2_9") (pintype "unspecified"))
      (node (ref "U6") (pin "14") (pinfunction "GRID2_14") (pintype "unspecified"))
    )
    (net (code "73") (name "Net-(LED7-DIG3)") (class "Default")
      (node (ref "LED7") (pin "8") (pinfunction "DIG3_8") (pintype "unspecified"))
      (node (ref "U6") (pin "13") (pinfunction "GRID3_13") (pintype "unspecified"))
    )
    (net (code "74") (name "Net-(LED7-DP)") (class "Default")
      (node (ref "LED7") (pin "3") (pinfunction "DP_3") (pintype "unspecified"))
      (node (ref "U6") (pin "9") (pinfunction "SG1KS8_9") (pintype "unspecified"))
    )
    (net (code "75") (name "Net-(LED7-E)") (class "Default")
      (node (ref "LED7") (pin "1") (pinfunction "E_1") (pintype "unspecified"))
      (node (ref "U6") (pin "6") (pinfunction "SG1KS5_6") (pintype "unspecified"))
    )
    (net (code "76") (name "Net-(LED7-F)") (class "Default")
      (node (ref "LED7") (pin "10") (pinfunction "F_10") (pintype "unspecified"))
      (node (ref "U6") (pin "7") (pinfunction "SG1KS6_7") (pintype "unspecified"))
    )
    (net (code "77") (name "Net-(LED7-G)") (class "Default")
      (node (ref "LED7") (pin "5") (pinfunction "G_5") (pintype "unspecified"))
      (node (ref "U6") (pin "8") (pinfunction "SG1KS7_8") (pintype "unspecified"))
    )
    (net (code "78") (name "Net-(LED8-A)") (class "Default")
      (node (ref "LED8") (pin "11") (pinfunction "A_11") (pintype "unspecified"))
      (node (ref "U7") (pin "2") (pinfunction "SG1KS1_2") (pintype "unspecified"))
    )
    (net (code "79") (name "Net-(LED8-B)") (class "Default")
      (node (ref "LED8") (pin "7") (pinfunction "B_7") (pintype "unspecified"))
      (node (ref "U7") (pin "3") (pinfunction "SG1KS2_3") (pintype "unspecified"))
    )
    (net (code "80") (name "Net-(LED8-C)") (class "Default")
      (node (ref "LED8") (pin "4") (pinfunction "C_4") (pintype "unspecified"))
      (node (ref "U7") (pin "4") (pinfunction "SG1KS3_4") (pintype "unspecified"))
    )
    (net (code "81") (name "Net-(LED8-D)") (class "Default")
      (node (ref "LED8") (pin "2") (pinfunction "D_2") (pintype "unspecified"))
      (node (ref "U7") (pin "5") (pinfunction "SG1KS4_5") (pintype "unspecified"))
    )
    (net (code "82") (name "Net-(LED8-DIG1)") (class "Default")
      (node (ref "LED8") (pin "12") (pinfunction "DIG1_12") (pintype "unspecified"))
      (node (ref "U7") (pin "15") (pinfunction "GRID1_15") (pintype "unspecified"))
    )
    (net (code "83") (name "Net-(LED8-DIG2)") (class "Default")
      (node (ref "LED8") (pin "9") (pinfunction "DIG2_9") (pintype "unspecified"))
      (node (ref "U7") (pin "14") (pinfunction "GRID2_14") (pintype "unspecified"))
    )
    (net (code "84") (name "Net-(LED8-DIG3)") (class "Default")
      (node (ref "LED8") (pin "8") (pinfunction "DIG3_8") (pintype "unspecified"))
      (node (ref "U7") (pin "13") (pinfunction "GRID3_13") (pintype "unspecified"))
    )
    (net (code "85") (name "Net-(LED8-DP)") (class "Default")
      (node (ref "LED8") (pin "3") (pinfunction "DP_3") (pintype "unspecified"))
      (node (ref "U7") (pin "9") (pinfunction "SG1KS8_9") (pintype "unspecified"))
    )
    (net (code "86") (name "Net-(LED8-E)") (class "Default")
      (node (ref "LED8") (pin "1") (pinfunction "E_1") (pintype "unspecified"))
      (node (ref "U7") (pin "6") (pinfunction "SG1KS5_6") (pintype "unspecified"))
    )
    (net (code "87") (name "Net-(LED8-F)") (class "Default")
      (node (ref "LED8") (pin "10") (pinfunction "F_10") (pintype "unspecified"))
      (node (ref "U7") (pin "7") (pinfunction "SG1KS6_7") (pintype "unspecified"))
    )
    (net (code "88") (name "Net-(LED8-G)") (class "Default")
      (node (ref "LED8") (pin "5") (pinfunction "G_5") (pintype "unspecified"))
      (node (ref "U7") (pin "8") (pinfunction "SG1KS7_8") (pintype "unspecified"))
    )
    (net (code "89") (name "Net-(LED9-A)") (class "Default")
      (node (ref "LED9") (pin "1") (pinfunction "A_1") (pintype "unspecified"))
      (node (ref "R22") (pin "2") (pinfunction "2_2") (pintype "unspecified"))
    )
    (net (code "90") (name "Net-(LED9-K)") (class "Default")
      (node (ref "H1") (pin "28") (pinfunction "28_28") (pintype "unspecified"))
      (node (ref "LED9") (pin "2") (pinfunction "K_2") (pintype "unspecified"))
    )
    (net (code "91") (name "Net-(LED10-A)") (class "Default")
      (node (ref "LED10") (pin "1") (pinfunction "A_1") (pintype "unspecified"))
      (node (ref "R24") (pin "2") (pinfunction "2_2") (pintype "unspecified"))
    )
    (net (code "92") (name "Net-(LED10-K)") (class "Default")
      (node (ref "H1") (pin "2") (pinfunction "2_2") (pintype "unspecified"))
      (node (ref "LED10") (pin "2") (pinfunction "K_2") (pintype "unspecified"))
    )
    (net (code "93") (name "Net-(LED11-A)") (class "Default")
      (node (ref "LED11") (pin "1") (pinfunction "A_1") (pintype "unspecified"))
      (node (ref "R25") (pin "2") (pinfunction "2_2") (pintype "unspecified"))
    )
    (net (code "94") (name "Net-(LED11-K)") (class "Default")
      (node (ref "H1") (pin "27") (pinfunction "27_27") (pintype "unspecified"))
      (node (ref "LED11") (pin "2") (pinfunction "K_2") (pintype "unspecified"))
    )
    (net (code "95") (name "Net-(LED12-A)") (class "Default")
      (node (ref "LED12") (pin "1") (pinfunction "A_1") (pintype "unspecified"))
      (node (ref "R26") (pin "2") (pinfunction "2_2") (pintype "unspecified"))
    )
    (net (code "96") (name "Net-(LED12-K)") (class "Default")
      (node (ref "H1") (pin "19") (pinfunction "19_19") (pintype "unspecified"))
      (node (ref "LED12") (pin "2") (pinfunction "K_2") (pintype "unspecified"))
    )
    (net (code "97") (name "Net-(LED13-A)") (class "Default")
      (node (ref "LED13") (pin "1") (pinfunction "A_1") (pintype "unspecified"))
      (node (ref "R27") (pin "2") (pinfunction "2_2") (pintype "unspecified"))
    )
    (net (code "98") (name "Net-(LED13-K)") (class "Default")
      (node (ref "H1") (pin "10") (pinfunction "10_10") (pintype "unspecified"))
      (node (ref "LED13") (pin "2") (pinfunction "K_2") (pintype "unspecified"))
    )
    (net (code "99") (name "Net-(LED14-A)") (class "Default")
      (node (ref "LED14") (pin "1") (pinfunction "A_1") (pintype "unspecified"))
      (node (ref "R28") (pin "2") (pinfunction "2_2") (pintype "unspecified"))
    )
    (net (code "100") (name "Net-(LED14-K)") (class "Default")
      (node (ref "H1") (pin "3") (pinfunction "3_3") (pintype "unspecified"))
      (node (ref "LED14") (pin "2") (pinfunction "K_2") (pintype "unspecified"))
    )
    (net (code "101") (name "Net-(LED15-A)") (class "Default")
      (node (ref "LED15") (pin "1") (pinfunction "A_1") (pintype "unspecified"))
      (node (ref "R29") (pin "2") (pinfunction "2_2") (pintype "unspecified"))
    )
    (net (code "102") (name "Net-(LED15-K)") (class "Default")
      (node (ref "H1") (pin "18") (pinfunction "18_18") (pintype "unspecified"))
      (node (ref "LED15") (pin "2") (pinfunction "K_2") (pintype "unspecified"))
    )
    (net (code "103") (name "Net-(LED16-A)") (class "Default")
      (node (ref "LED16") (pin "1") (pinfunction "A_1") (pintype "unspecified"))
      (node (ref "R30") (pin "2") (pinfunction "2_2") (pintype "unspecified"))
    )
    (net (code "104") (name "Net-(LED16-K)") (class "Default")
      (node (ref "H1") (pin "26") (pinfunction "26_26") (pintype "unspecified"))
      (node (ref "LED16") (pin "2") (pinfunction "K_2") (pintype "unspecified"))
    )
    (net (code "105") (name "Net-(LED17-A)") (class "Default")
      (node (ref "LED17") (pin "1") (pinfunction "A_1") (pintype "unspecified"))
      (node (ref "R31") (pin "2") (pinfunction "2_2") (pintype "unspecified"))
    )
    (net (code "106") (name "Net-(LED17-K)") (class "Default")
      (node (ref "H1") (pin "9") (pinfunction "9_9") (pintype "unspecified"))
      (node (ref "LED17") (pin "2") (pinfunction "K_2") (pintype "unspecified"))
    )
    (net (code "107") (name "Net-(R12-Pad1)") (class "Default")
      (node (ref "R12") (pin "1") (pinfunction "1_1") (pintype "unspecified"))
      (node (ref "SW1") (pin "5") (pinfunction "5_5") (pintype "unspecified"))
    )
    (net (code "108") (name "Net-(R13-Pad1)") (class "Default")
      (node (ref "R13") (pin "1") (pinfunction "1_1") (pintype "unspecified"))
      (node (ref "SW3") (pin "5") (pinfunction "5_5") (pintype "unspecified"))
    )
    (net (code "109") (name "Net-(R14-Pad1)") (class "Default")
      (node (ref "R14") (pin "1") (pinfunction "1_1") (pintype "unspecified"))
      (node (ref "SW2") (pin "5") (pinfunction "5_5") (pintype "unspecified"))
    )
    (net (code "110") (name "Net-(R16-Pad1)") (class "Default")
      (node (ref "R16") (pin "1") (pinfunction "1_1") (pintype "unspecified"))
      (node (ref "SW4") (pin "5") (pinfunction "5_5") (pintype "unspecified"))
    )
    (net (code "111") (name "Net-(R21-Pad1)") (class "Default")
      (node (ref "R21") (pin "1") (pinfunction "1_1") (pintype "unspecified"))
      (node (ref "SW5") (pin "5") (pinfunction "5_5") (pintype "unspecified"))
    )
    (net (code "112") (name "Net-(U4-CLK)") (class "Default")
      (node (ref "C6") (pin "1") (pinfunction "1_1") (pintype "unspecified"))
      (node (ref "H2") (pin "30") (pinfunction "30_30") (pintype "unspecified"))
      (node (ref "R4") (pin "1") (pinfunction "1_1") (pintype "unspecified"))
      (node (ref "U4") (pin "18") (pinfunction "CLK_18") (pintype "unspecified"))
    )
    (net (code "113") (name "Net-(U4-DIO)") (class "Default")
      (node (ref "C5") (pin "1") (pinfunction "1_1") (pintype "unspecified"))
      (node (ref "H2") (pin "31") (pinfunction "31_31") (pintype "unspecified"))
      (node (ref "R3") (pin "1") (pinfunction "1_1") (pintype "unspecified"))
      (node (ref "U4") (pin "17") (pinfunction "DIO_17") (pintype "unspecified"))
    )
    (net (code "114") (name "Net-(U4-VDD)") (class "Default")
      (node (ref "C1") (pin "2") (pinfunction "2_2") (pintype "unspecified"))
      (node (ref "C11") (pin "2") (pinfunction "2_2") (pintype "unspecified"))
      (node (ref "C12") (pin "2") (pinfunction "2_2") (pintype "unspecified"))
      (node (ref "C15") (pin "2") (pinfunction "2_2") (pintype "unspecified"))
      (node (ref "C16") (pin "2") (pinfunction "2_2") (pintype "unspecified"))
      (node (ref "C2") (pin "2") (pinfunction "2_2") (pintype "unspecified"))
      (node (ref "C7") (pin "2") (pinfunction "2_2") (pintype "unspecified"))
      (node (ref "C8") (pin "2") (pinfunction "2_2") (pintype "unspecified"))
      (node (ref "H2") (pin "34") (pinfunction "34_34") (pintype "unspecified"))
      (node (ref "R1") (pin "2") (pinfunction "2_2") (pintype "unspecified"))
      (node (ref "R12") (pin "2") (pinfunction "2_2") (pintype "unspecified"))
      (node (ref "R13") (pin "2") (pinfunction "2_2") (pintype "unspecified"))
      (node (ref "R14") (pin "2") (pinfunction "2_2") (pintype "unspecified"))
      (node (ref "R16") (pin "2") (pinfunction "2_2") (pintype "unspecified"))
      (node (ref "R17") (pin "2") (pinfunction "2_2") (pintype "unspecified"))
      (node (ref "R18") (pin "2") (pinfunction "2_2") (pintype "unspecified"))
      (node (ref "R19") (pin "2") (pinfunction "2_2") (pintype "unspecified"))
      (node (ref "R2") (pin "2") (pinfunction "2_2") (pintype "unspecified"))
      (node (ref "R20") (pin "2") (pinfunction "2_2") (pintype "unspecified"))
      (node (ref "R3") (pin "2") (pinfunction "2_2") (pintype "unspecified"))
      (node (ref "R4") (pin "2") (pinfunction "2_2") (pintype "unspecified"))
      (node (ref "R5") (pin "2") (pinfunction "2_2") (pintype "unspecified"))
      (node (ref "R6") (pin "2") (pinfunction "2_2") (pintype "unspecified"))
      (node (ref "R7") (pin "2") (pinfunction "2_2") (pintype "unspecified"))
      (node (ref "R8") (pin "2") (pinfunction "2_2") (pintype "unspecified"))
      (node (ref "U4") (pin "16") (pinfunction "VDD_16") (pintype "unspecified"))
      (node (ref "U5") (pin "16") (pinfunction "VDD_16") (pintype "unspecified"))
      (node (ref "U6") (pin "16") (pinfunction "VDD_16") (pintype "unspecified"))
      (node (ref "U7") (pin "16") (pinfunction "VDD_16") (pintype "unspecified"))
    )
    (net (code "115") (name "Net-(U5-CLK)") (class "Default")
      (node (ref "C3") (pin "1") (pinfunction "1_1") (pintype "unspecified"))
      (node (ref "H2") (pin "33") (pinfunction "33_33") (pintype "unspecified"))
      (node (ref "R1") (pin "1") (pinfunction "1_1") (pintype "unspecified"))
      (node (ref "U5") (pin "18") (pinfunction "CLK_18") (pintype "unspecified"))
    )
    (net (code "116") (name "Net-(U5-DIO)") (class "Default")
      (node (ref "C4") (pin "1") (pinfunction "1_1") (pintype "unspecified"))
      (node (ref "H2") (pin "32") (pinfunction "32_32") (pintype "unspecified"))
      (node (ref "R2") (pin "1") (pinfunction "1_1") (pintype "unspecified"))
      (node (ref "U5") (pin "17") (pinfunction "DIO_17") (pintype "unspecified"))
    )
    (net (code "117") (name "Net-(U6-CLK)") (class "Default")
      (node (ref "C10") (pin "1") (pinfunction "1_1") (pintype "unspecified"))
      (node (ref "H2") (pin "29") (pinfunction "29_29") (pintype "unspecified"))
      (node (ref "R6") (pin "1") (pinfunction "1_1") (pintype "unspecified"))
      (node (ref "U6") (pin "18") (pinfunction "CLK_18") (pintype "unspecified"))
    )
    (net (code "118") (name "Net-(U6-DIO)") (class "Default")
      (node (ref "C9") (pin "1") (pinfunction "1_1") (pintype "unspecified"))
      (node (ref "H2") (pin "28") (pinfunction "28_28") (pintype "unspecified"))
      (node (ref "R5") (pin "1") (pinfunction "1_1") (pintype "unspecified"))
      (node (ref "U6") (pin "17") (pinfunction "DIO_17") (pintype "unspecified"))
    )
    (net (code "119") (name "Net-(U7-CLK)") (class "Default")
      (node (ref "C14") (pin "1") (pinfunction "1_1") (pintype "unspecified"))
      (node (ref "H2") (pin "26") (pinfunction "26_26") (pintype "unspecified"))
      (node (ref "R8") (pin "1") (pinfunction "1_1") (pintype "unspecified"))
      (node (ref "U7") (pin "18") (pinfunction "CLK_18") (pintype "unspecified"))
    )
    (net (code "120") (name "Net-(U7-DIO)") (class "Default")
      (node (ref "C13") (pin "1") (pinfunction "1_1") (pintype "unspecified"))
      (node (ref "H2") (pin "27") (pinfunction "27_27") (pintype "unspecified"))
      (node (ref "R7") (pin "1") (pinfunction "1_1") (pintype "unspecified"))
      (node (ref "U7") (pin "17") (pinfunction "DIO_17") (pintype "unspecified"))
    )
    (net (code "121") (name "Net-(VR1-CW)") (class "Default")
      (node (ref "H2") (pin "19") (pinfunction "19_19") (pintype "unspecified"))
      (node (ref "VR1") (pin "3") (pinfunction "CW_3") (pintype "bidirectional"))
      (node (ref "VR2") (pin "3") (pinfunction "CW_3") (pintype "bidirectional"))
    )
    (net (code "122") (name "Net-(VR1-NO_2)") (class "Default")
      (node (ref "H2") (pin "20") (pinfunction "20_20") (pintype "unspecified"))
      (node (ref "VR1") (pin "5") (pinfunction "NO_2_5") (pintype "bidirectional"))
    )
    (net (code "123") (name "Net-(VR1-WIPER)") (class "Default")
      (node (ref "H2") (pin "18") (pinfunction "18_18") (pintype "unspecified"))
      (node (ref "VR1") (pin "2") (pinfunction "WIPER_2") (pintype "bidirectional"))
    )
    (net (code "124") (name "Net-(VR2-NO_2)") (class "Default")
      (node (ref "H2") (pin "17") (pinfunction "17_17") (pintype "unspecified"))
      (node (ref "VR2") (pin "5") (pinfunction "NO_2_5") (pintype "bidirectional"))
    )
    (net (code "125") (name "Net-(VR2-WIPER)") (class "Default")
      (node (ref "H2") (pin "16") (pinfunction "16_16") (pintype "unspecified"))
      (node (ref "VR2") (pin "2") (pinfunction "WIPER_2") (pintype "bidirectional"))
    )
    (net (code "126") (name "unconnected-(H1-Pad30)") (class "Default")
      (node (ref "H1") (pin "30") (pinfunction "30_30") (pintype "unspecified"))
    )
    (net (code "127") (name "unconnected-(H1-Pad31)") (class "Default")
      (node (ref "H1") (pin "31") (pinfunction "31_31") (pintype "unspecified"))
    )
    (net (code "128") (name "unconnected-(H1-Pad32)") (class "Default")
      (node (ref "H1") (pin "32") (pinfunction "32_32") (pintype "unspecified"))
    )
    (net (code "129") (name "unconnected-(H1-Pad33)") (class "Default")
      (node (ref "H1") (pin "33") (pinfunction "33_33") (pintype "unspecified"))
    )
    (net (code "130") (name "unconnected-(H1-Pad34)") (class "Default")
      (node (ref "H1") (pin "34") (pinfunction "34_34") (pintype "unspecified"))
    )
    (net (code "131") (name "unconnected-(L1-B-Pad2)") (class "Default")
      (node (ref "L1") (pin "2") (pinfunction "B_2") (pintype "unspecified"))
    )
    (net (code "132") (name "unconnected-(SW1-Pad1)") (class "Default")
      (node (ref "SW1") (pin "1") (pinfunction "1_1") (pintype "unspecified"))
    )
    (net (code "133") (name "unconnected-(SW1-Pad4)") (class "Default")
      (node (ref "SW1") (pin "4") (pinfunction "4_4") (pintype "unspecified"))
    )
    (net (code "134") (name "unconnected-(SW2-Pad1)") (class "Default")
      (node (ref "SW2") (pin "1") (pinfunction "1_1") (pintype "unspecified"))
    )
    (net (code "135") (name "unconnected-(SW2-Pad4)") (class "Default")
      (node (ref "SW2") (pin "4") (pinfunction "4_4") (pintype "unspecified"))
    )
    (net (code "136") (name "unconnected-(SW3-Pad1)") (class "Default")
      (node (ref "SW3") (pin "1") (pinfunction "1_1") (pintype "unspecified"))
    )
    (net (code "137") (name "unconnected-(SW3-Pad4)") (class "Default")
      (node (ref "SW3") (pin "4") (pinfunction "4_4") (pintype "unspecified"))
    )
    (net (code "138") (name "unconnected-(SW4-Pad1)") (class "Default")
      (node (ref "SW4") (pin "1") (pinfunction "1_1") (pintype "unspecified"))
    )
    (net (code "139") (name "unconnected-(SW4-Pad4)") (class "Default")
      (node (ref "SW4") (pin "4") (pinfunction "4_4") (pintype "unspecified"))
    )
    (net (code "140") (name "unconnected-(SW5-Pad1)") (class "Default")
      (node (ref "SW5") (pin "1") (pinfunction "1_1") (pintype "unspecified"))
    )
    (net (code "141") (name "unconnected-(SW5-Pad4)") (class "Default")
      (node (ref "SW5") (pin "4") (pinfunction "4_4") (pintype "unspecified"))
    )
    (net (code "142") (name "unconnected-(SW6-Pad1)") (class "Default")
      (node (ref "SW6") (pin "1") (pinfunction "1_1") (pintype "unspecified"))
    )
    (net (code "143") (name "unconnected-(SW6-Pad4)") (class "Default")
      (node (ref "SW6") (pin "4") (pinfunction "4_4") (pintype "unspecified"))
    )
    (net (code "144") (name "unconnected-(SW6-Pad5)") (class "Default")
      (node (ref "SW6") (pin "5") (pinfunction "5_5") (pintype "unspecified"))
    )
    (net (code "145") (name "unconnected-(SW6-Pad6)") (class "Default")
      (node (ref "SW6") (pin "6") (pinfunction "6_6") (pintype "unspecified"))
    )
    (net (code "146") (name "unconnected-(U4-GRID4-Pad12)") (class "Default")
      (node (ref "U4") (pin "12") (pinfunction "GRID4_12") (pintype "unspecified"))
    )
    (net (code "147") (name "unconnected-(U4-GRID5-Pad11)") (class "Default")
      (node (ref "U4") (pin "11") (pinfunction "GRID5_11") (pintype "unspecified"))
    )
    (net (code "148") (name "unconnected-(U4-GRID6-Pad10)") (class "Default")
      (node (ref "U4") (pin "10") (pinfunction "GRID6_10") (pintype "unspecified"))
    )
    (net (code "149") (name "unconnected-(U4-K1-Pad19)") (class "Default")
      (node (ref "U4") (pin "19") (pinfunction "K1_19") (pintype "unspecified"))
    )
    (net (code "150") (name "unconnected-(U4-K2-Pad20)") (class "Default")
      (node (ref "U4") (pin "20") (pinfunction "K2_20") (pintype "unspecified"))
    )
    (net (code "151") (name "unconnected-(U5-GRID4-Pad12)") (class "Default")
      (node (ref "U5") (pin "12") (pinfunction "GRID4_12") (pintype "unspecified"))
    )
    (net (code "152") (name "unconnected-(U5-GRID5-Pad11)") (class "Default")
      (node (ref "U5") (pin "11") (pinfunction "GRID5_11") (pintype "unspecified"))
    )
    (net (code "153") (name "unconnected-(U5-GRID6-Pad10)") (class "Default")
      (node (ref "U5") (pin "10") (pinfunction "GRID6_10") (pintype "unspecified"))
    )
    (net (code "154") (name "unconnected-(U5-K1-Pad19)") (class "Default")
      (node (ref "U5") (pin "19") (pinfunction "K1_19") (pintype "unspecified"))
    )
    (net (code "155") (name "unconnected-(U5-K2-Pad20)") (class "Default")
      (node (ref "U5") (pin "20") (pinfunction "K2_20") (pintype "unspecified"))
    )
    (net (code "156") (name "unconnected-(U6-GRID4-Pad12)") (class "Default")
      (node (ref "U6") (pin "12") (pinfunction "GRID4_12") (pintype "unspecified"))
    )
    (net (code "157") (name "unconnected-(U6-GRID5-Pad11)") (class "Default")
      (node (ref "U6") (pin "11") (pinfunction "GRID5_11") (pintype "unspecified"))
    )
    (net (code "158") (name "unconnected-(U6-GRID6-Pad10)") (class "Default")
      (node (ref "U6") (pin "10") (pinfunction "GRID6_10") (pintype "unspecified"))
    )
    (net (code "159") (name "unconnected-(U6-K1-Pad19)") (class "Default")
      (node (ref "U6") (pin "19") (pinfunction "K1_19") (pintype "unspecified"))
    )
    (net (code "160") (name "unconnected-(U6-K2-Pad20)") (class "Default")
      (node (ref "U6") (pin "20") (pinfunction "K2_20") (pintype "unspecified"))
    )
    (net (code "161") (name "unconnected-(U7-GRID4-Pad12)") (class "Default")
      (node (ref "U7") (pin "12") (pinfunction "GRID4_12") (pintype "unspecified"))
    )
    (net (code "162") (name "unconnected-(U7-GRID5-Pad11)") (class "Default")
      (node (ref "U7") (pin "11") (pinfunction "GRID5_11") (pintype "unspecified"))
    )
    (net (code "163") (name "unconnected-(U7-GRID6-Pad10)") (class "Default")
      (node (ref "U7") (pin "10") (pinfunction "GRID6_10") (pintype "unspecified"))
    )
    (net (code "164") (name "unconnected-(U7-K1-Pad19)") (class "Default")
      (node (ref "U7") (pin "19") (pinfunction "K1_19") (pintype "unspecified"))
    )
    (net (code "165") (name "unconnected-(U7-K2-Pad20)") (class "Default")
      (node (ref "U7") (pin "20") (pinfunction "K2_20") (pintype "unspecified"))
    )
    (net (code "166") (name "unconnected-(VR1-PadMH1)") (class "Default")
      (node (ref "VR1") (pin "MH1") (pinfunction "MH1_MH1") (pintype "bidirectional"))
    )
    (net (code "167") (name "unconnected-(VR1-PadMH2)") (class "Default")
      (node (ref "VR1") (pin "MH2") (pinfunction "MH2_MH2") (pintype "bidirectional"))
    )
    (net (code "168") (name "unconnected-(VR2-PadMH1)") (class "Default")
      (node (ref "VR2") (pin "MH1") (pinfunction "MH1_MH1") (pintype "bidirectional"))
    )
    (net (code "169") (name "unconnected-(VR2-PadMH2)") (class "Default")
      (node (ref "VR2") (pin "MH2") (pinfunction "MH2_MH2") (pintype "bidirectional"))
    )
  )
)
